# 7segement2digits1badidea-mk-4_1.net
KiCad netlist of a schematic drawn in EAGLE
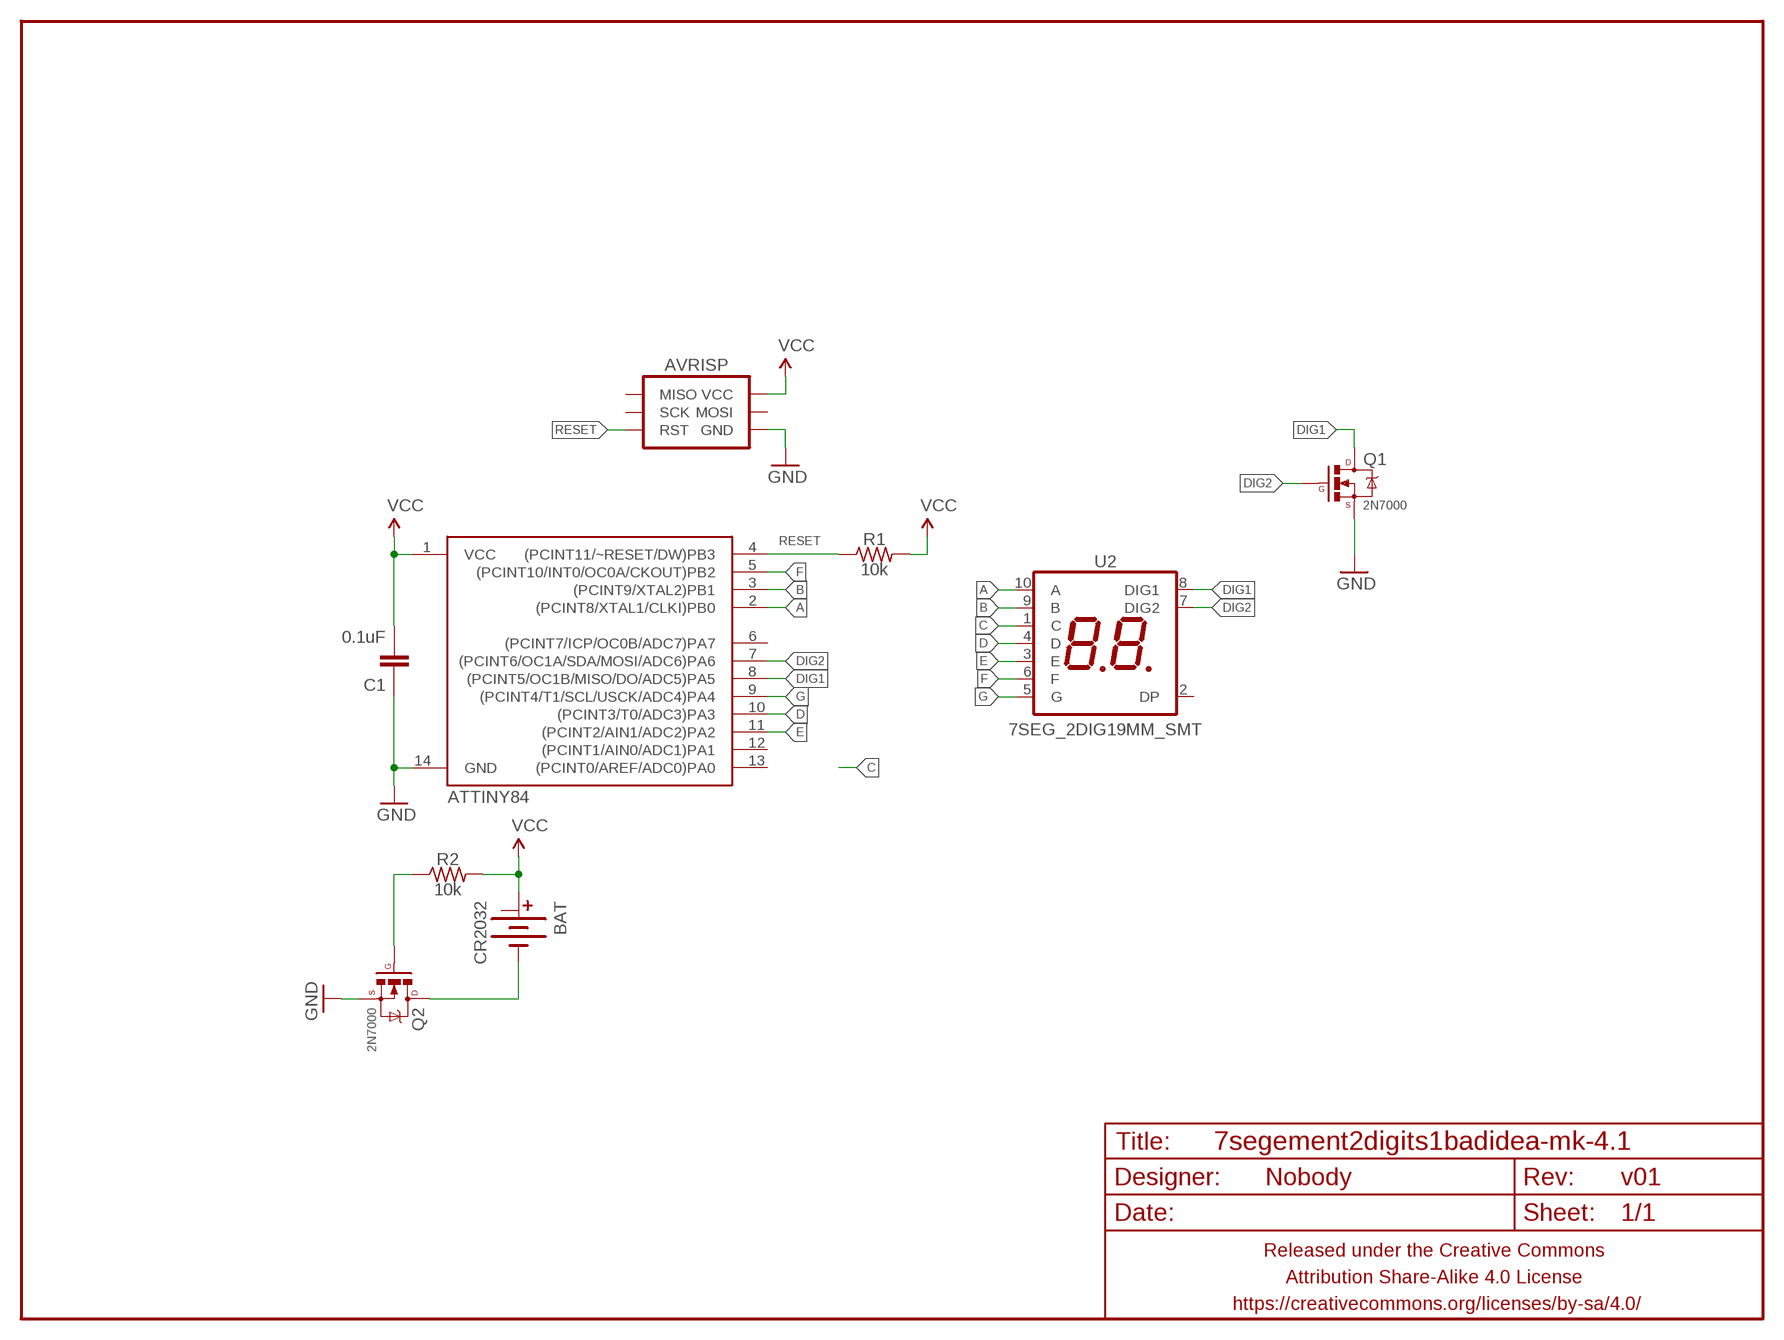
[diagram p0: schematic, sheet 1]

(export (version "E")
  (design (tool "Eeschema 10.0.6"))
  (components
    (comp (ref "AVRISP")
      (value "AVR_SPI_PRG_6PTH")
      (footprint "eagle-import:2X3")
      (libsource (lib "eagle-import") (part "AVR_SPI_PRG_6PTH"))
    )
    (comp (ref "BAT")
      (value "CR2032")
      (footprint "eagle-import:BATTCON_20MM_MINE_STAHPIT")
      (libsource (lib "eagle-import") (part "BATTERY-COINCR2032_SMD_TIGHT"))
    )
    (comp (ref "C1")
      (value "0.1uF")
      (footprint "eagle-import:C0805")
      (libsource (lib "eagle-import") (part "CAPACITOR-CERAMICC0805"))
    )
    (comp (ref "FRAME1")
      (value "FRAME-LETTERNO_PACKAGE")
      (footprint "eagle-import:DUMMY")
      (fields (field (name "DESIGNER") "Nobody"))
      (libsource (lib "eagle-import") (part "FRAME-LETTERNO_PACKAGE"))
    )
    (comp (ref "Q1")
      (value "2N7000")
      (footprint "eagle-import:SOT23")
      (libsource (lib "eagle-import") (part "MOSFET-NCHANNELBSS123LT1G"))
    )
    (comp (ref "Q2")
      (value "2N7000")
      (footprint "eagle-import:SOT23")
      (libsource (lib "eagle-import") (part "MOSFET-NCHANNELBSS123LT1G"))
    )
    (comp (ref "R1")
      (value "10k")
      (footprint "eagle-import:R0805")
      (libsource (lib "eagle-import") (part "RESISTORR0805"))
    )
    (comp (ref "R2")
      (value "10k")
      (footprint "eagle-import:R0805")
      (libsource (lib "eagle-import") (part "RESISTORR0805"))
    )
    (comp (ref "U1")
      (value "ATTINY84")
      (footprint "eagle-import:SO14")
      (libsource (lib "eagle-import") (part "ATTINY84"))
    )
    (comp (ref "U2")
      (value "7SEG_2DIG19MM_SMT")
      (footprint "eagle-import:7SEG_2DIG_19MM_SMT")
      (libsource (lib "eagle-import") (part "7SEG_2DIG19MM_SMT"))
    )
  )
  (nets
    (net (code "1") (name "A") (class "Default")
      (node (ref "U1") (pin "2") (pinfunction "(PCINT8/XTAL1/CLKI)PB0_2") (pintype "bidirectional"))
      (node (ref "U2") (pin "10") (pinfunction "A_10") (pintype "passive"))
    )
    (net (code "2") (name "B") (class "Default")
      (node (ref "U1") (pin "3") (pinfunction "(PCINT9/XTAL2)PB1_3") (pintype "bidirectional"))
      (node (ref "U2") (pin "9") (pinfunction "B_9") (pintype "passive"))
    )
    (net (code "3") (name "C") (class "Default")
      (node (ref "U2") (pin "1") (pinfunction "C_1") (pintype "passive"))
    )
    (net (code "4") (name "D") (class "Default")
      (node (ref "U1") (pin "10") (pinfunction "(PCINT3/T0/ADC3)PA3_10") (pintype "bidirectional"))
      (node (ref "U2") (pin "4") (pinfunction "D_4") (pintype "passive"))
    )
    (net (code "5") (name "DIG1") (class "Default")
      (node (ref "Q1") (pin "3") (pinfunction "D_3") (pintype "passive"))
      (node (ref "U1") (pin "8") (pinfunction "(PCINT5/OC1B/MISO/DO/ADC5)PA5_8") (pintype "bidirectional"))
      (node (ref "U2") (pin "8") (pinfunction "DIG1_8") (pintype "passive"))
    )
    (net (code "6") (name "DIG2") (class "Default")
      (node (ref "Q1") (pin "1") (pinfunction "G_1") (pintype "passive"))
      (node (ref "U1") (pin "7") (pinfunction "(PCINT6/OC1A/SDA/MOSI/ADC6)PA6_7") (pintype "bidirectional"))
      (node (ref "U2") (pin "7") (pinfunction "DIG2_7") (pintype "passive"))
    )
    (net (code "7") (name "E") (class "Default")
      (node (ref "U1") (pin "11") (pinfunction "(PCINT2/AIN1/ADC2)PA2_11") (pintype "bidirectional"))
      (node (ref "U2") (pin "3") (pinfunction "E_3") (pintype "passive"))
    )
    (net (code "8") (name "F") (class "Default")
      (node (ref "U1") (pin "5") (pinfunction "(PCINT10/INT0/OC0A/CKOUT)PB2_5") (pintype "bidirectional"))
      (node (ref "U2") (pin "6") (pinfunction "F_6") (pintype "passive"))
    )
    (net (code "9") (name "G") (class "Default")
      (node (ref "U1") (pin "9") (pinfunction "(PCINT4/T1/SCL/USCK/ADC4)PA4_9") (pintype "bidirectional"))
      (node (ref "U2") (pin "5") (pinfunction "G_5") (pintype "passive"))
    )
    (net (code "10") (name "GND") (class "Default")
      (node (ref "AVRISP") (pin "6") (pinfunction "GND_6") (pintype "passive"))
      (node (ref "C1") (pin "1") (pinfunction "1_1") (pintype "passive"))
      (node (ref "Q1") (pin "2") (pinfunction "S_2") (pintype "passive"))
      (node (ref "Q2") (pin "2") (pinfunction "S_2") (pintype "passive"))
      (node (ref "U1") (pin "14") (pinfunction "GND_14") (pintype "bidirectional"))
    )
    (net (code "11") (name "Net-(BAT--)") (class "Default")
      (node (ref "BAT") (pin "BOTTOM") (pinfunction "-_BOTTOM") (pintype "bidirectional"))
      (node (ref "Q2") (pin "3") (pinfunction "D_3") (pintype "passive"))
    )
    (net (code "12") (name "Net-(Q2-G)") (class "Default")
      (node (ref "Q2") (pin "1") (pinfunction "G_1") (pintype "passive"))
      (node (ref "R2") (pin "1") (pinfunction "1_1") (pintype "passive"))
    )
    (net (code "13") (name "RESET") (class "Default")
      (node (ref "AVRISP") (pin "5") (pinfunction "RST_5") (pintype "passive"))
      (node (ref "R1") (pin "1") (pinfunction "1_1") (pintype "passive"))
      (node (ref "U1") (pin "4") (pinfunction "(PCINT11/~{RESET/DW})PB3_4") (pintype "bidirectional"))
    )
    (net (code "14") (name "VCC") (class "Default")
      (node (ref "AVRISP") (pin "2") (pinfunction "VCC_2") (pintype "passive"))
      (node (ref "BAT") (pin "TOP@1") (pinfunction "+_TOP@1") (pintype "bidirectional"))
      (node (ref "C1") (pin "2") (pinfunction "2_2") (pintype "passive"))
      (node (ref "R1") (pin "2") (pinfunction "2_2") (pintype "passive"))
      (node (ref "R2") (pin "2") (pinfunction "2_2") (pintype "passive"))
      (node (ref "U1") (pin "1") (pinfunction "VCC_1") (pintype "bidirectional"))
    )
    (net (code "15") (name "unconnected-(AVRISP-MISO-Pad1)") (class "Default")
      (node (ref "AVRISP") (pin "1") (pinfunction "MISO_1") (pintype "passive"))
    )
    (net (code "16") (name "unconnected-(AVRISP-MOSI-Pad4)") (class "Default")
      (node (ref "AVRISP") (pin "4") (pinfunction "MOSI_4") (pintype "passive"))
    )
    (net (code "17") (name "unconnected-(AVRISP-SCK-Pad3)") (class "Default")
      (node (ref "AVRISP") (pin "3") (pinfunction "SCK_3") (pintype "passive"))
    )
    (net (code "18") (name "unconnected-(BAT-+1-PadTOP@2)") (class "Default")
      (node (ref "BAT") (pin "TOP@2") (pinfunction "+1_TOP@2") (pintype "bidirectional"))
    )
    (net (code "19") (name "unconnected-(U1-(PCINT0{slash}AREF{slash}ADC0)PA0-Pad13)") (class "Default")
      (node (ref "U1") (pin "13") (pinfunction "(PCINT0/AREF/ADC0)PA0_13") (pintype "bidirectional"))
    )
    (net (code "20") (name "unconnected-(U1-(PCINT1{slash}AIN0{slash}ADC1)PA1-Pad12)") (class "Default")
      (node (ref "U1") (pin "12") (pinfunction "(PCINT1/AIN0/ADC1)PA1_12") (pintype "bidirectional"))
    )
    (net (code "21") (name "unconnected-(U1-(PCINT7{slash}ICP{slash}OC0B{slash}ADC7)PA7-Pad6)") (class "Default")
      (node (ref "U1") (pin "6") (pinfunction "(PCINT7/ICP/OC0B/ADC7)PA7_6") (pintype "bidirectional"))
    )
    (net (code "22") (name "unconnected-(U2-DP-Pad2)") (class "Default")
      (node (ref "U2") (pin "2") (pinfunction "DP_2") (pintype "passive"))
    )
  )
)
